# ETRX_FECU.net
KiCad netlist of a schematic drawn in Altium Designer
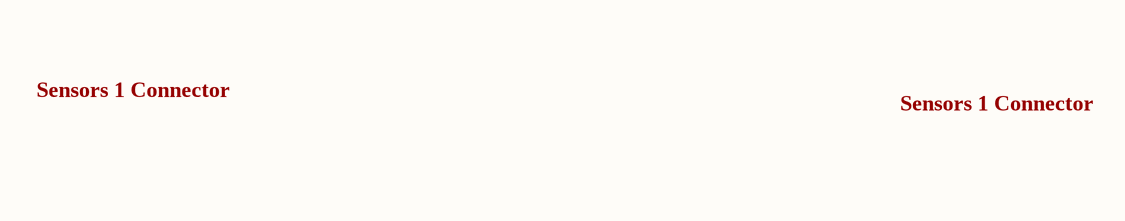
[diagram p0: ETRX_FECU.SchDoc, left]
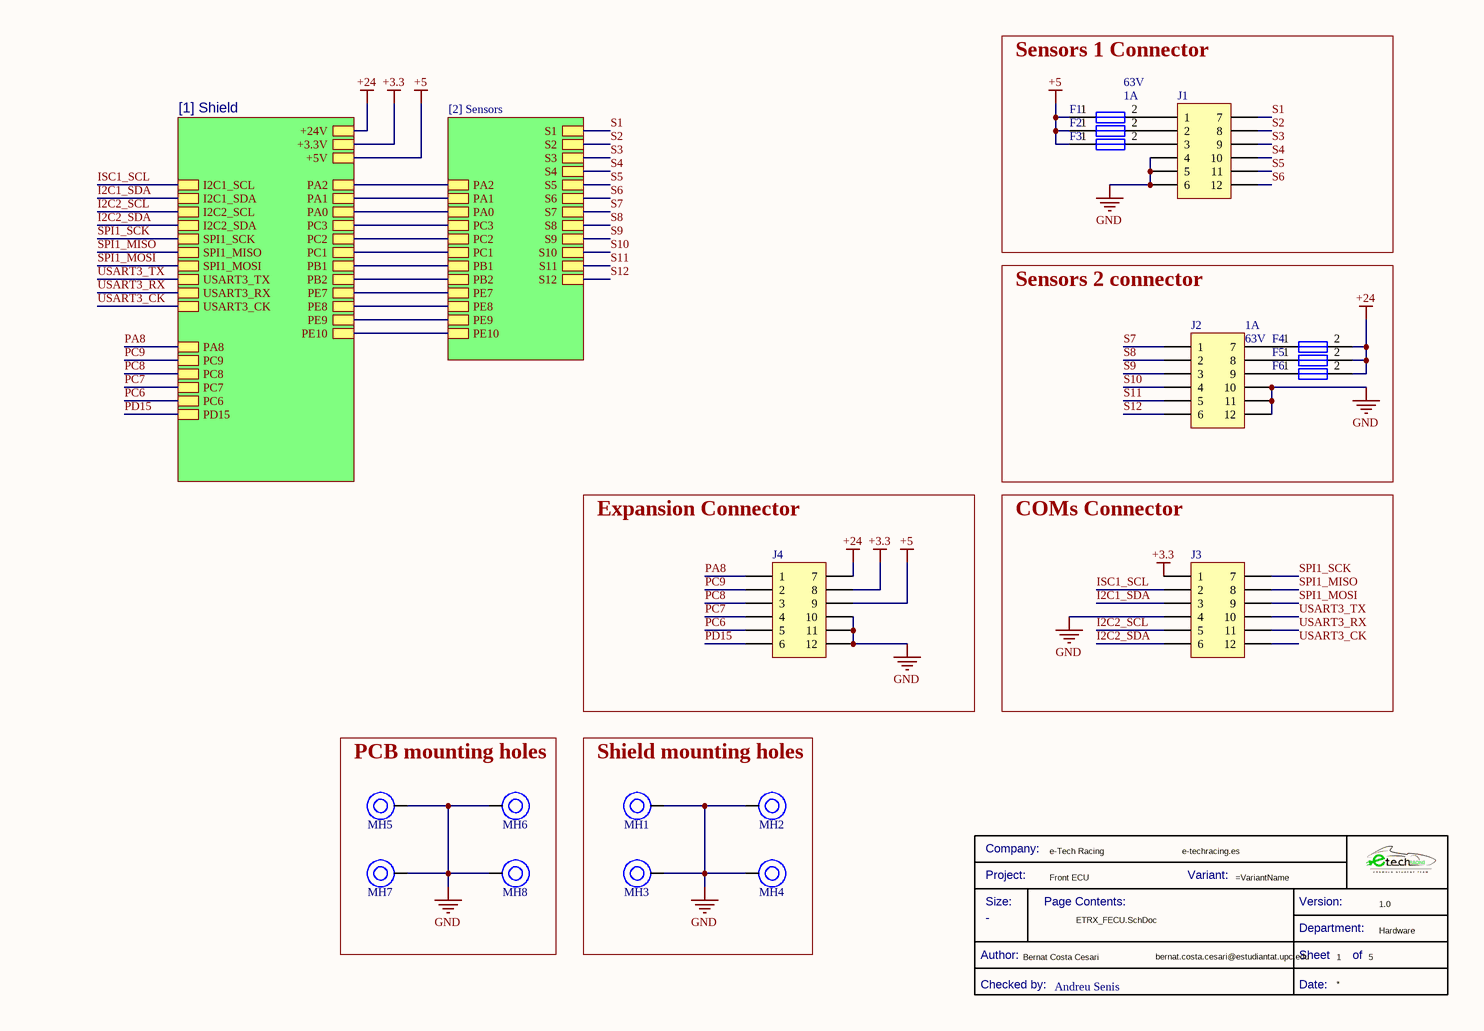
[diagram p1: ETRX_FECU.SchDoc, right]

(export (version "E")
  (design (tool "Eeschema 10.0.6"))
  (components
    (comp (ref "F1")
      (value "0437001.WRA")
      (footprint "Fuse_1206")
      (description "Fuse Chip Fast Acting 1A 63V SMD Solder Pad 1206 Ceramic T/R Automotive")
      (fields
        (field (name "MANUFACTURER") "Littelfuse")
        (field (name "CURRENT RATING") "1A")
        (field (name "VOLTAGE RATING (DC)") "63V")
        (field (name ".CREATOR") "DO")
      )
      (libsource (lib "Filter components") (part "Fuse_1A_63V_1206"))
    )
    (comp (ref "F2")
      (value "0437001.WRA")
      (footprint "Fuse_1206")
      (description "Fuse Chip Fast Acting 1A 63V SMD Solder Pad 1206 Ceramic T/R Automotive")
      (fields (field (name "MANUFACTURER") "Littelfuse") (field (name ".CREATOR") "DO"))
      (libsource (lib "Filter components") (part "Fuse_1A_63V_1206"))
    )
    (comp (ref "F3")
      (value "0437001.WRA")
      (footprint "Fuse_1206")
      (description "Fuse Chip Fast Acting 1A 63V SMD Solder Pad 1206 Ceramic T/R Automotive")
      (fields (field (name "MANUFACTURER") "Littelfuse") (field (name ".CREATOR") "DO"))
      (libsource (lib "Filter components") (part "Fuse_1A_63V_1206"))
    )
    (comp (ref "F4")
      (value "0437001.WRA")
      (footprint "Fuse_1206")
      (description "Fuse Chip Fast Acting 1A 63V SMD Solder Pad 1206 Ceramic T/R Automotive")
      (fields
        (field (name "MANUFACTURER") "Littelfuse")
        (field (name "CURRENT RATING") "1A")
        (field (name "VOLTAGE RATING (DC)") "63V")
        (field (name ".CREATOR") "DO")
      )
      (libsource (lib "Filter components") (part "Fuse_1A_63V_1206"))
    )
    (comp (ref "F5")
      (value "0437001.WRA")
      (footprint "Fuse_1206")
      (description "Fuse Chip Fast Acting 1A 63V SMD Solder Pad 1206 Ceramic T/R Automotive")
      (fields (field (name "MANUFACTURER") "Littelfuse") (field (name ".CREATOR") "DO"))
      (libsource (lib "Filter components") (part "Fuse_1A_63V_1206"))
    )
    (comp (ref "F6")
      (value "0437001.WRA")
      (footprint "Fuse_1206")
      (description "Fuse Chip Fast Acting 1A 63V SMD Solder Pad 1206 Ceramic T/R Automotive")
      (fields (field (name "MANUFACTURER") "Littelfuse") (field (name ".CREATOR") "DO"))
      (libsource (lib "Filter components") (part "Fuse_1A_63V_1206"))
    )
    (comp (ref "J1")
      (value "1053101112")
      (footprint "J_NanoFit_2x6_V")
      (libsource (lib "Electromechanical") (part "J_NanoFit_2x6_V"))
    )
    (comp (ref "J2")
      (value "1053101112")
      (footprint "J_NanoFit_2x6_V")
      (libsource (lib "Electromechanical") (part "J_NanoFit_2x6_V"))
    )
    (comp (ref "J3")
      (value "1053101112")
      (footprint "J_NanoFit_2x6_V")
      (libsource (lib "Electromechanical") (part "J_NanoFit_2x6_V"))
    )
    (comp (ref "J4")
      (value "1053101112")
      (footprint "J_NanoFit_2x6_V")
      (libsource (lib "Electromechanical") (part "J_NanoFit_2x6_V"))
    )
    (comp (ref "MH1")
      (value "Mounting_Hole_M3")
      (footprint "Mounting_Hole_M3")
      (libsource (lib "Electromechanical") (part "Mounting_Hole_M3"))
    )
    (comp (ref "MH2")
      (value "Mounting_Hole_M3")
      (footprint "Mounting_Hole_M3")
      (libsource (lib "Electromechanical") (part "Mounting_Hole_M3"))
    )
    (comp (ref "MH3")
      (value "Mounting_Hole_M3")
      (footprint "Mounting_Hole_M3")
      (libsource (lib "Electromechanical") (part "Mounting_Hole_M3"))
    )
    (comp (ref "MH4")
      (value "Mounting_Hole_M3")
      (footprint "Mounting_Hole_M3")
      (libsource (lib "Electromechanical") (part "Mounting_Hole_M3"))
    )
    (comp (ref "MH5")
      (value "Mounting_Hole_M4")
      (footprint "Mounting_Hole_M4")
      (libsource (lib "Electromechanical") (part "Mounting_Hole_M4"))
    )
    (comp (ref "MH6")
      (value "Mounting_Hole_M4")
      (footprint "Mounting_Hole_M4")
      (libsource (lib "Electromechanical") (part "Mounting_Hole_M4"))
    )
    (comp (ref "MH7")
      (value "Mounting_Hole_M4")
      (footprint "Mounting_Hole_M4")
      (libsource (lib "Electromechanical") (part "Mounting_Hole_M4"))
    )
    (comp (ref "MH8")
      (value "Mounting_Hole_M4")
      (footprint "Mounting_Hole_M4")
      (libsource (lib "Electromechanical") (part "Mounting_Hole_M4"))
    )
  )
  (nets
    (net (code "1") (name "+3.3") (class "Default")
      (node (ref "J3") (pin "1") (pinfunction "1_1") (pintype "passive"))
      (node (ref "J4") (pin "8") (pinfunction "8_8") (pintype "passive"))
    )
    (net (code "2") (name "+5") (class "Default")
      (node (ref "F1") (pin "1") (pinfunction "1_1") (pintype "passive"))
      (node (ref "F2") (pin "1") (pinfunction "1_1") (pintype "passive"))
      (node (ref "F3") (pin "1") (pinfunction "1_1") (pintype "passive"))
      (node (ref "J4") (pin "9") (pinfunction "9_9") (pintype "passive"))
    )
    (net (code "3") (name "+24") (class "Default")
      (node (ref "F4") (pin "2") (pinfunction "2_2") (pintype "passive"))
      (node (ref "F5") (pin "2") (pinfunction "2_2") (pintype "passive"))
      (node (ref "F6") (pin "2") (pinfunction "2_2") (pintype "passive"))
      (node (ref "J4") (pin "7") (pinfunction "7_7") (pintype "passive"))
    )
    (net (code "4") (name "/I2C1_SDA") (class "Default")
      (node (ref "J3") (pin "3") (pinfunction "3_3") (pintype "passive"))
    )
    (net (code "5") (name "/I2C2_SCL") (class "Default")
      (node (ref "J3") (pin "5") (pinfunction "5_5") (pintype "passive"))
    )
    (net (code "6") (name "/I2C2_SDA") (class "Default")
      (node (ref "J3") (pin "6") (pinfunction "6_6") (pintype "passive"))
    )
    (net (code "7") (name "/ISC1_SCL") (class "Default")
      (node (ref "J3") (pin "2") (pinfunction "2_2") (pintype "passive"))
    )
    (net (code "11") (name "/PA8") (class "Default")
      (node (ref "J4") (pin "1") (pinfunction "1_1") (pintype "passive"))
    )
    (net (code "17") (name "/PC6") (class "Default")
      (node (ref "J4") (pin "5") (pinfunction "5_5") (pintype "passive"))
    )
    (net (code "18") (name "/PC7") (class "Default")
      (node (ref "J4") (pin "4") (pinfunction "4_4") (pintype "passive"))
    )
    (net (code "19") (name "/PC8") (class "Default")
      (node (ref "J4") (pin "3") (pinfunction "3_3") (pintype "passive"))
    )
    (net (code "20") (name "/PC9") (class "Default")
      (node (ref "J4") (pin "2") (pinfunction "2_2") (pintype "passive"))
    )
    (net (code "21") (name "/PD15") (class "Default")
      (node (ref "J4") (pin "6") (pinfunction "6_6") (pintype "passive"))
    )
    (net (code "26") (name "/S1") (class "Default")
      (node (ref "J1") (pin "7") (pinfunction "7_7") (pintype "passive"))
    )
    (net (code "27") (name "/S2") (class "Default")
      (node (ref "J1") (pin "8") (pinfunction "8_8") (pintype "passive"))
    )
    (net (code "28") (name "/S3") (class "Default")
      (node (ref "J1") (pin "9") (pinfunction "9_9") (pintype "passive"))
    )
    (net (code "29") (name "/S4") (class "Default")
      (node (ref "J1") (pin "10") (pinfunction "10_10") (pintype "passive"))
    )
    (net (code "30") (name "/S5") (class "Default")
      (node (ref "J1") (pin "11") (pinfunction "11_11") (pintype "passive"))
    )
    (net (code "31") (name "/S6") (class "Default")
      (node (ref "J1") (pin "12") (pinfunction "12_12") (pintype "passive"))
    )
    (net (code "32") (name "/S7") (class "Default")
      (node (ref "J2") (pin "1") (pinfunction "1_1") (pintype "passive"))
    )
    (net (code "33") (name "/S8") (class "Default")
      (node (ref "J2") (pin "2") (pinfunction "2_2") (pintype "passive"))
    )
    (net (code "34") (name "/S9") (class "Default")
      (node (ref "J2") (pin "3") (pinfunction "3_3") (pintype "passive"))
    )
    (net (code "35") (name "/S10") (class "Default")
      (node (ref "J2") (pin "4") (pinfunction "4_4") (pintype "passive"))
    )
    (net (code "36") (name "/S11") (class "Default")
      (node (ref "J2") (pin "5") (pinfunction "5_5") (pintype "passive"))
    )
    (net (code "37") (name "/S12") (class "Default")
      (node (ref "J2") (pin "6") (pinfunction "6_6") (pintype "passive"))
    )
    (net (code "38") (name "/SPI1_MISO") (class "Default")
      (node (ref "J3") (pin "8") (pinfunction "8_8") (pintype "passive"))
    )
    (net (code "39") (name "/SPI1_MOSI") (class "Default")
      (node (ref "J3") (pin "9") (pinfunction "9_9") (pintype "passive"))
    )
    (net (code "40") (name "/SPI1_SCK") (class "Default")
      (node (ref "J3") (pin "7") (pinfunction "7_7") (pintype "passive"))
    )
    (net (code "41") (name "/USART3_CK") (class "Default")
      (node (ref "J3") (pin "12") (pinfunction "12_12") (pintype "passive"))
    )
    (net (code "42") (name "/USART3_RX") (class "Default")
      (node (ref "J3") (pin "11") (pinfunction "11_11") (pintype "passive"))
    )
    (net (code "43") (name "/USART3_TX") (class "Default")
      (node (ref "J3") (pin "10") (pinfunction "10_10") (pintype "passive"))
    )
    (net (code "44") (name "GND") (class "Default")
      (node (ref "J1") (pin "4") (pinfunction "4_4") (pintype "passive"))
      (node (ref "J1") (pin "5") (pinfunction "5_5") (pintype "passive"))
      (node (ref "J1") (pin "6") (pinfunction "6_6") (pintype "passive"))
      (node (ref "J2") (pin "10") (pinfunction "10_10") (pintype "passive"))
      (node (ref "J2") (pin "11") (pinfunction "11_11") (pintype "passive"))
      (node (ref "J2") (pin "12") (pinfunction "12_12") (pintype "passive"))
      (node (ref "J3") (pin "4") (pinfunction "4_4") (pintype "passive"))
      (node (ref "J4") (pin "10") (pinfunction "10_10") (pintype "passive"))
      (node (ref "J4") (pin "11") (pinfunction "11_11") (pintype "passive"))
      (node (ref "J4") (pin "12") (pinfunction "12_12") (pintype "passive"))
      (node (ref "MH1") (pin "1") (pinfunction "1_1") (pintype "passive"))
      (node (ref "MH2") (pin "1") (pinfunction "1_1") (pintype "passive"))
      (node (ref "MH3") (pin "1") (pinfunction "1_1") (pintype "passive"))
      (node (ref "MH4") (pin "1") (pinfunction "1_1") (pintype "passive"))
      (node (ref "MH5") (pin "1") (pinfunction "1_1") (pintype "passive"))
      (node (ref "MH6") (pin "1") (pinfunction "1_1") (pintype "passive"))
      (node (ref "MH7") (pin "1") (pinfunction "1_1") (pintype "passive"))
      (node (ref "MH8") (pin "1") (pinfunction "1_1") (pintype "passive"))
    )
    (net (code "45") (name "Net-(F1-Pad2)") (class "Default")
      (node (ref "F1") (pin "2") (pinfunction "2_2") (pintype "passive"))
      (node (ref "J1") (pin "1") (pinfunction "1_1") (pintype "passive"))
    )
    (net (code "46") (name "Net-(F2-Pad2)") (class "Default")
      (node (ref "F2") (pin "2") (pinfunction "2_2") (pintype "passive"))
      (node (ref "J1") (pin "2") (pinfunction "2_2") (pintype "passive"))
    )
    (net (code "47") (name "Net-(F3-Pad2)") (class "Default")
      (node (ref "F3") (pin "2") (pinfunction "2_2") (pintype "passive"))
      (node (ref "J1") (pin "3") (pinfunction "3_3") (pintype "passive"))
    )
    (net (code "48") (name "Net-(F4-Pad1)") (class "Default")
      (node (ref "F4") (pin "1") (pinfunction "1_1") (pintype "passive"))
      (node (ref "J2") (pin "7") (pinfunction "7_7") (pintype "passive"))
    )
    (net (code "49") (name "Net-(F5-Pad1)") (class "Default")
      (node (ref "F5") (pin "1") (pinfunction "1_1") (pintype "passive"))
      (node (ref "J2") (pin "8") (pinfunction "8_8") (pintype "passive"))
    )
    (net (code "50") (name "Net-(F6-Pad1)") (class "Default")
      (node (ref "F6") (pin "1") (pinfunction "1_1") (pintype "passive"))
      (node (ref "J2") (pin "9") (pinfunction "9_9") (pintype "passive"))
    )
  )
)
